# JAD_1_0.net
KiCad netlist of a schematic drawn in EAGLE
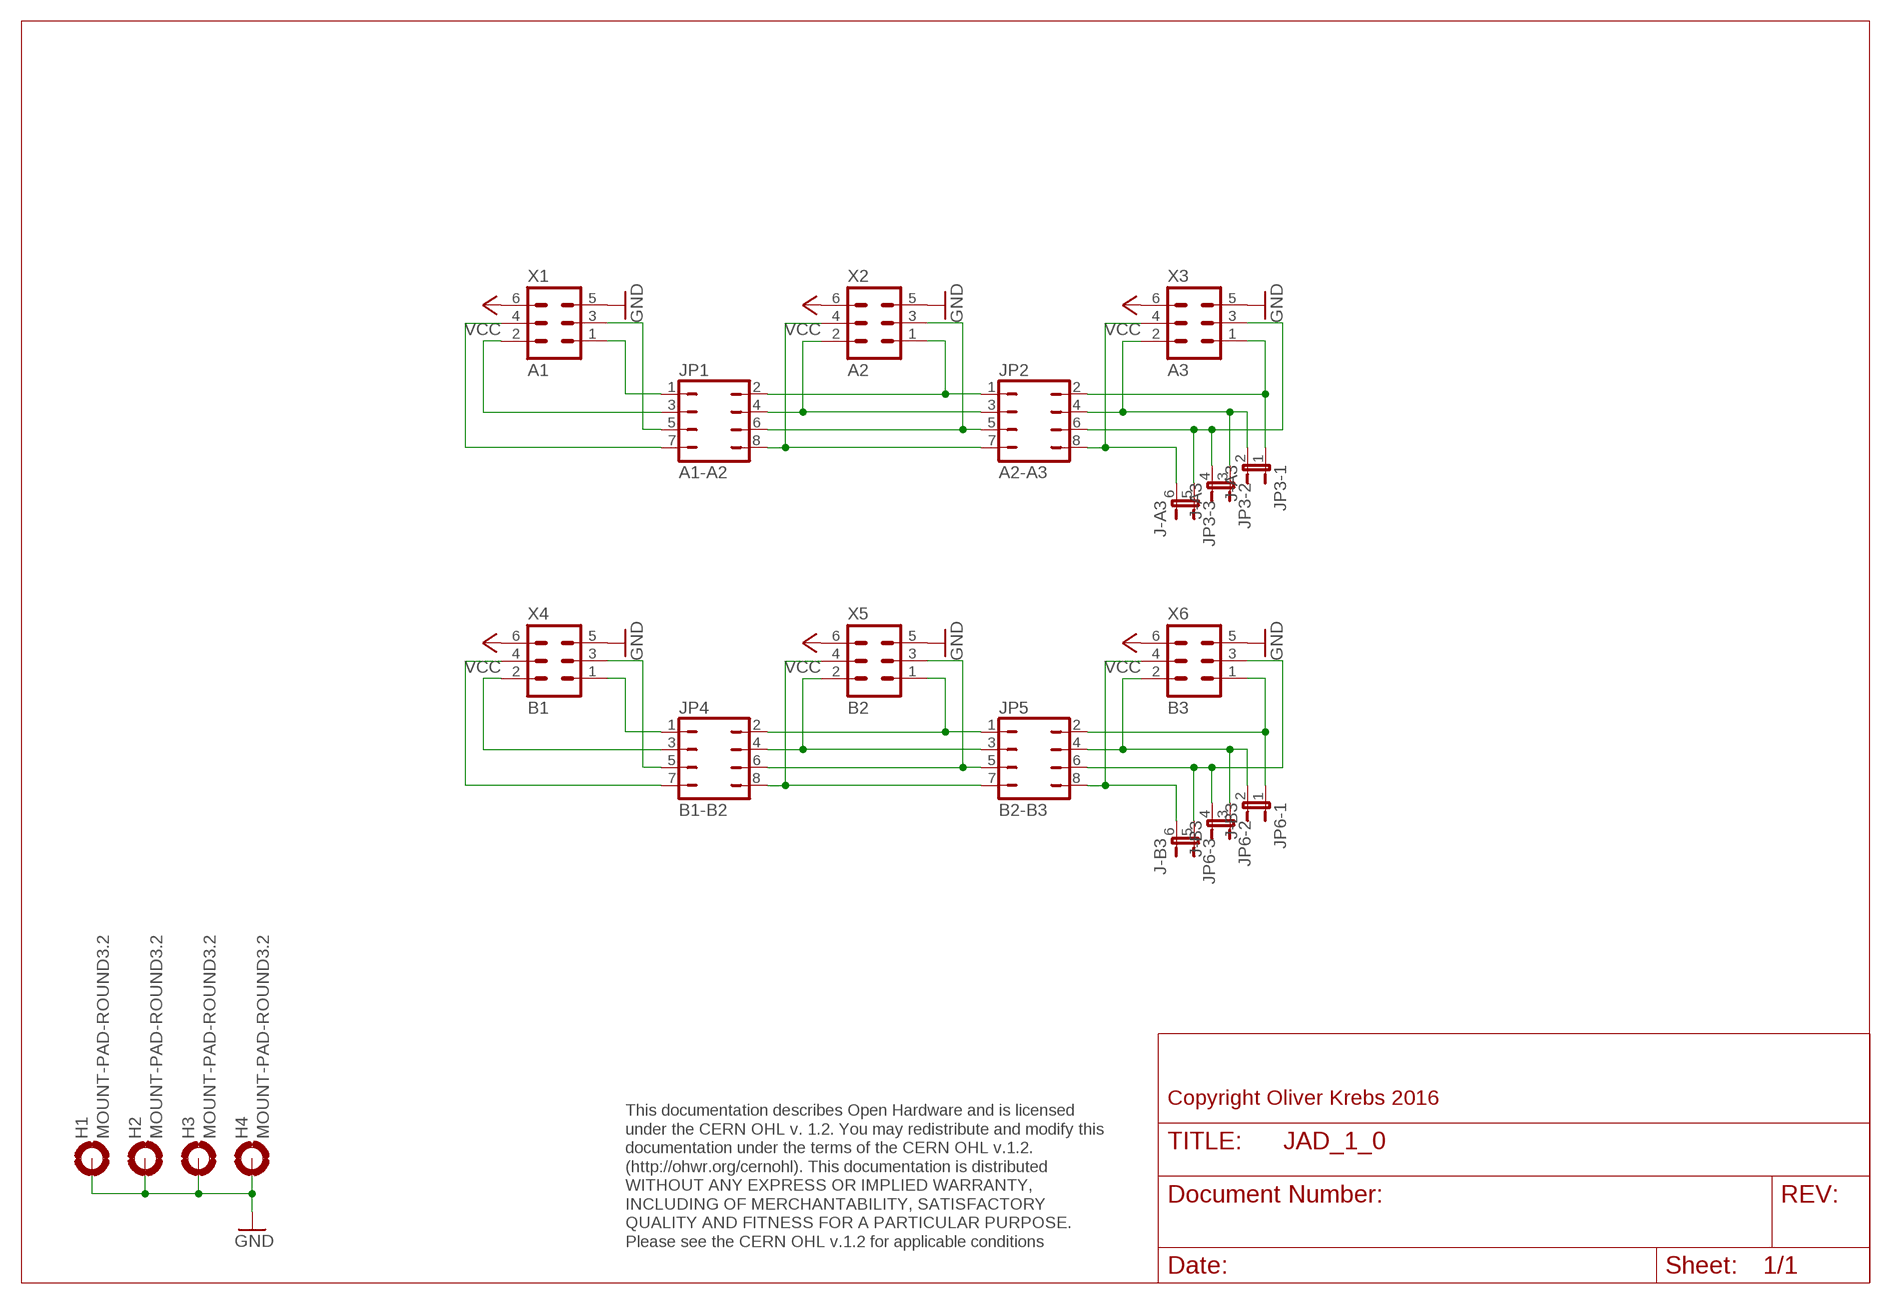
[diagram p0: schematic, sheet 1]

(export (version "E")
  (design (tool "Eeschema 10.0.6"))
  (components
    (comp (ref "H1")
      (value "MOUNT-PAD-ROUND3.2")
      (footprint "eagle-import:3,2-PAD")
      (libsource (lib "eagle-import") (part "MOUNT-PAD-ROUND3.2"))
    )
    (comp (ref "H2")
      (value "MOUNT-PAD-ROUND3.2")
      (footprint "eagle-import:3,2-PAD")
      (libsource (lib "eagle-import") (part "MOUNT-PAD-ROUND3.2"))
    )
    (comp (ref "H3")
      (value "MOUNT-PAD-ROUND3.2")
      (footprint "eagle-import:3,2-PAD")
      (libsource (lib "eagle-import") (part "MOUNT-PAD-ROUND3.2"))
    )
    (comp (ref "H4")
      (value "MOUNT-PAD-ROUND3.2")
      (footprint "eagle-import:3,2-PAD")
      (libsource (lib "eagle-import") (part "MOUNT-PAD-ROUND3.2"))
    )
    (comp (ref "JP1")
      (value "A1-A2")
      (footprint "eagle-import:JP4Q")
      (libsource (lib "eagle-import") (part "JP4Q"))
    )
    (comp (ref "JP2")
      (value "A2-A3")
      (footprint "eagle-import:JP4Q")
      (libsource (lib "eagle-import") (part "JP4Q"))
    )
    (comp (ref "JP3")
      (value "J-A3")
      (footprint "eagle-import:JP3Q")
      (libsource (lib "eagle-import") (part "JP3QE"))
    )
    (comp (ref "JP4")
      (value "B1-B2")
      (footprint "eagle-import:JP4Q")
      (libsource (lib "eagle-import") (part "JP4Q"))
    )
    (comp (ref "JP5")
      (value "B2-B3")
      (footprint "eagle-import:JP4Q")
      (libsource (lib "eagle-import") (part "JP4Q"))
    )
    (comp (ref "JP6")
      (value "J-B3")
      (footprint "eagle-import:JP3Q")
      (libsource (lib "eagle-import") (part "JP3QE"))
    )
    (comp (ref "X1")
      (value "A1")
      (footprint "eagle-import:ML-6")
      (libsource (lib "eagle-import") (part "ML6"))
    )
    (comp (ref "X2")
      (value "A2")
      (footprint "eagle-import:ML-6")
      (libsource (lib "eagle-import") (part "ML6"))
    )
    (comp (ref "X3")
      (value "A3")
      (footprint "eagle-import:ML-6")
      (libsource (lib "eagle-import") (part "ML6"))
    )
    (comp (ref "X4")
      (value "B1")
      (footprint "eagle-import:ML-6")
      (libsource (lib "eagle-import") (part "ML6"))
    )
    (comp (ref "X5")
      (value "B2")
      (footprint "eagle-import:ML-6")
      (libsource (lib "eagle-import") (part "ML6"))
    )
    (comp (ref "X6")
      (value "B3")
      (footprint "eagle-import:ML-6")
      (libsource (lib "eagle-import") (part "ML6"))
    )
  )
  (nets
    (net (code "1") (name "GND") (class "Default")
      (node (ref "H1") (pin "B3,2") (pinfunction "MOUNT_B3,2") (pintype "passive"))
      (node (ref "H2") (pin "B3,2") (pinfunction "MOUNT_B3,2") (pintype "passive"))
      (node (ref "H3") (pin "B3,2") (pinfunction "MOUNT_B3,2") (pintype "passive"))
      (node (ref "H4") (pin "B3,2") (pinfunction "MOUNT_B3,2") (pintype "passive"))
      (node (ref "X1") (pin "5") (pinfunction "5_5") (pintype "passive"))
      (node (ref "X2") (pin "5") (pinfunction "5_5") (pintype "passive"))
      (node (ref "X3") (pin "5") (pinfunction "5_5") (pintype "passive"))
      (node (ref "X4") (pin "5") (pinfunction "5_5") (pintype "passive"))
      (node (ref "X5") (pin "5") (pinfunction "5_5") (pintype "passive"))
      (node (ref "X6") (pin "5") (pinfunction "5_5") (pintype "passive"))
    )
    (net (code "2") (name "Net-(JP1-Pad1)") (class "Default")
      (node (ref "JP1") (pin "1") (pinfunction "1_1") (pintype "passive"))
      (node (ref "X1") (pin "1") (pinfunction "1_1") (pintype "passive"))
    )
    (net (code "3") (name "Net-(JP1-Pad2)") (class "Default")
      (node (ref "JP1") (pin "2") (pinfunction "2_2") (pintype "passive"))
      (node (ref "JP2") (pin "1") (pinfunction "1_1") (pintype "passive"))
      (node (ref "X2") (pin "1") (pinfunction "1_1") (pintype "passive"))
    )
    (net (code "4") (name "Net-(JP1-Pad3)") (class "Default")
      (node (ref "JP1") (pin "3") (pinfunction "3_3") (pintype "passive"))
      (node (ref "X1") (pin "2") (pinfunction "2_2") (pintype "passive"))
    )
    (net (code "5") (name "Net-(JP1-Pad4)") (class "Default")
      (node (ref "JP1") (pin "4") (pinfunction "4_4") (pintype "passive"))
      (node (ref "JP2") (pin "3") (pinfunction "3_3") (pintype "passive"))
      (node (ref "X2") (pin "2") (pinfunction "2_2") (pintype "passive"))
    )
    (net (code "6") (name "Net-(JP1-Pad5)") (class "Default")
      (node (ref "JP1") (pin "5") (pinfunction "5_5") (pintype "passive"))
      (node (ref "X1") (pin "3") (pinfunction "3_3") (pintype "passive"))
    )
    (net (code "7") (name "Net-(JP1-Pad6)") (class "Default")
      (node (ref "JP1") (pin "6") (pinfunction "6_6") (pintype "passive"))
      (node (ref "JP2") (pin "5") (pinfunction "5_5") (pintype "passive"))
      (node (ref "X2") (pin "3") (pinfunction "3_3") (pintype "passive"))
    )
    (net (code "8") (name "Net-(JP1-Pad7)") (class "Default")
      (node (ref "JP1") (pin "7") (pinfunction "7_7") (pintype "passive"))
      (node (ref "X1") (pin "4") (pinfunction "4_4") (pintype "passive"))
    )
    (net (code "9") (name "Net-(JP1-Pad8)") (class "Default")
      (node (ref "JP1") (pin "8") (pinfunction "8_8") (pintype "passive"))
      (node (ref "JP2") (pin "7") (pinfunction "7_7") (pintype "passive"))
      (node (ref "X2") (pin "4") (pinfunction "4_4") (pintype "passive"))
    )
    (net (code "10") (name "Net-(JP2-Pad2)") (class "Default")
      (node (ref "JP2") (pin "2") (pinfunction "2_2") (pintype "passive"))
      (node (ref "JP3") (pin "1") (pinfunction "1_1") (pintype "passive"))
      (node (ref "X3") (pin "1") (pinfunction "1_1") (pintype "passive"))
    )
    (net (code "11") (name "Net-(JP3B-1)") (class "Default")
      (node (ref "JP2") (pin "4") (pinfunction "4_4") (pintype "passive"))
      (node (ref "JP3") (pin "2") (pinfunction "2_2") (pintype "passive"))
      (node (ref "JP3") (pin "3") (pinfunction "1_3") (pintype "passive"))
      (node (ref "X3") (pin "2") (pinfunction "2_2") (pintype "passive"))
    )
    (net (code "12") (name "Net-(JP3B-2)") (class "Default")
      (node (ref "JP2") (pin "6") (pinfunction "6_6") (pintype "passive"))
      (node (ref "JP3") (pin "4") (pinfunction "2_4") (pintype "passive"))
      (node (ref "JP3") (pin "5") (pinfunction "1_5") (pintype "passive"))
      (node (ref "X3") (pin "3") (pinfunction "3_3") (pintype "passive"))
    )
    (net (code "13") (name "Net-(JP3C-2)") (class "Default")
      (node (ref "JP2") (pin "8") (pinfunction "8_8") (pintype "passive"))
      (node (ref "JP3") (pin "6") (pinfunction "2_6") (pintype "passive"))
      (node (ref "X3") (pin "4") (pinfunction "4_4") (pintype "passive"))
    )
    (net (code "14") (name "Net-(JP4-Pad1)") (class "Default")
      (node (ref "JP4") (pin "1") (pinfunction "1_1") (pintype "passive"))
      (node (ref "X4") (pin "1") (pinfunction "1_1") (pintype "passive"))
    )
    (net (code "15") (name "Net-(JP4-Pad2)") (class "Default")
      (node (ref "JP4") (pin "2") (pinfunction "2_2") (pintype "passive"))
      (node (ref "JP5") (pin "1") (pinfunction "1_1") (pintype "passive"))
      (node (ref "X5") (pin "1") (pinfunction "1_1") (pintype "passive"))
    )
    (net (code "16") (name "Net-(JP4-Pad3)") (class "Default")
      (node (ref "JP4") (pin "3") (pinfunction "3_3") (pintype "passive"))
      (node (ref "X4") (pin "2") (pinfunction "2_2") (pintype "passive"))
    )
    (net (code "17") (name "Net-(JP4-Pad4)") (class "Default")
      (node (ref "JP4") (pin "4") (pinfunction "4_4") (pintype "passive"))
      (node (ref "JP5") (pin "3") (pinfunction "3_3") (pintype "passive"))
      (node (ref "X5") (pin "2") (pinfunction "2_2") (pintype "passive"))
    )
    (net (code "18") (name "Net-(JP4-Pad5)") (class "Default")
      (node (ref "JP4") (pin "5") (pinfunction "5_5") (pintype "passive"))
      (node (ref "X4") (pin "3") (pinfunction "3_3") (pintype "passive"))
    )
    (net (code "19") (name "Net-(JP4-Pad6)") (class "Default")
      (node (ref "JP4") (pin "6") (pinfunction "6_6") (pintype "passive"))
      (node (ref "JP5") (pin "5") (pinfunction "5_5") (pintype "passive"))
      (node (ref "X5") (pin "3") (pinfunction "3_3") (pintype "passive"))
    )
    (net (code "20") (name "Net-(JP4-Pad7)") (class "Default")
      (node (ref "JP4") (pin "7") (pinfunction "7_7") (pintype "passive"))
      (node (ref "X4") (pin "4") (pinfunction "4_4") (pintype "passive"))
    )
    (net (code "21") (name "Net-(JP4-Pad8)") (class "Default")
      (node (ref "JP4") (pin "8") (pinfunction "8_8") (pintype "passive"))
      (node (ref "JP5") (pin "7") (pinfunction "7_7") (pintype "passive"))
      (node (ref "X5") (pin "4") (pinfunction "4_4") (pintype "passive"))
    )
    (net (code "22") (name "Net-(JP5-Pad2)") (class "Default")
      (node (ref "JP5") (pin "2") (pinfunction "2_2") (pintype "passive"))
      (node (ref "JP6") (pin "1") (pinfunction "1_1") (pintype "passive"))
      (node (ref "X6") (pin "1") (pinfunction "1_1") (pintype "passive"))
    )
    (net (code "23") (name "Net-(JP6B-1)") (class "Default")
      (node (ref "JP5") (pin "4") (pinfunction "4_4") (pintype "passive"))
      (node (ref "JP6") (pin "2") (pinfunction "2_2") (pintype "passive"))
      (node (ref "JP6") (pin "3") (pinfunction "1_3") (pintype "passive"))
      (node (ref "X6") (pin "2") (pinfunction "2_2") (pintype "passive"))
    )
    (net (code "24") (name "Net-(JP6B-2)") (class "Default")
      (node (ref "JP5") (pin "6") (pinfunction "6_6") (pintype "passive"))
      (node (ref "JP6") (pin "4") (pinfunction "2_4") (pintype "passive"))
      (node (ref "JP6") (pin "5") (pinfunction "1_5") (pintype "passive"))
      (node (ref "X6") (pin "3") (pinfunction "3_3") (pintype "passive"))
    )
    (net (code "25") (name "Net-(JP6C-2)") (class "Default")
      (node (ref "JP5") (pin "8") (pinfunction "8_8") (pintype "passive"))
      (node (ref "JP6") (pin "6") (pinfunction "2_6") (pintype "passive"))
      (node (ref "X6") (pin "4") (pinfunction "4_4") (pintype "passive"))
    )
    (net (code "26") (name "VCC") (class "Default")
      (node (ref "X1") (pin "6") (pinfunction "6_6") (pintype "passive"))
      (node (ref "X2") (pin "6") (pinfunction "6_6") (pintype "passive"))
      (node (ref "X3") (pin "6") (pinfunction "6_6") (pintype "passive"))
      (node (ref "X4") (pin "6") (pinfunction "6_6") (pintype "passive"))
      (node (ref "X5") (pin "6") (pinfunction "6_6") (pintype "passive"))
      (node (ref "X6") (pin "6") (pinfunction "6_6") (pintype "passive"))
    )
  )
)
